# nucleo_power_supply_schematic.net
KiCad netlist of a schematic drawn in EAGLE
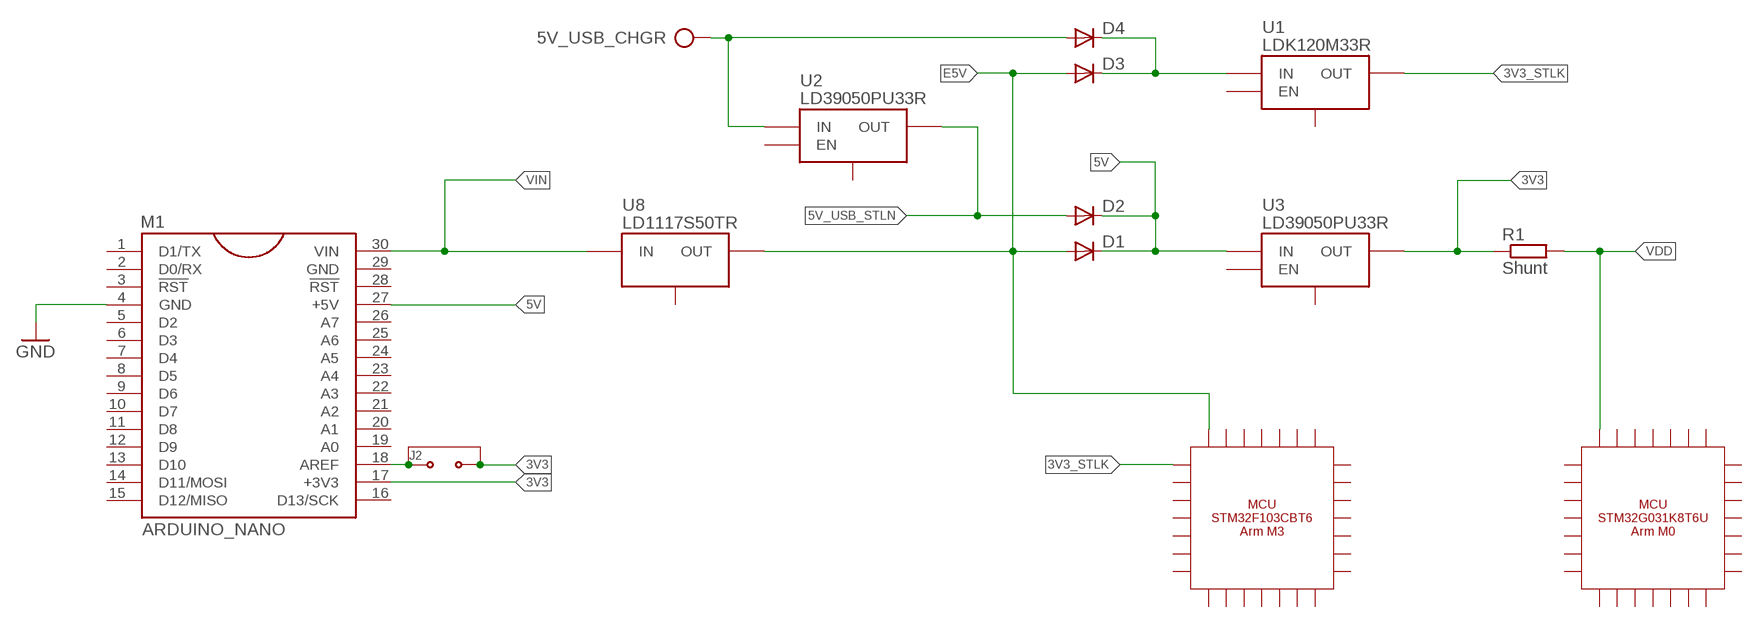
[diagram p0: schematic, sheet 1]

(export (version "E")
  (design (tool "Eeschema 10.0.6"))
  (components
    (comp (ref "D1") (value "D") (footprint "eagle-import:1X02") (libsource (lib "eagle-import") (part "D")))
    (comp (ref "D2") (value "D") (footprint "eagle-import:1X02") (libsource (lib "eagle-import") (part "D")))
    (comp (ref "D3") (value "D") (footprint "eagle-import:1X02") (libsource (lib "eagle-import") (part "D")))
    (comp (ref "D4") (value "D") (footprint "eagle-import:1X02") (libsource (lib "eagle-import") (part "D")))
    (comp (ref "J2")
      (value "CON-J2")
      (footprint "eagle-import:CON-HEADER-M-RM254-1X02")
      (libsource (lib "eagle-import") (part "CON-J2"))
    )
    (comp (ref "M1")
      (value "ARDUINO_NANO")
      (footprint "eagle-import:ARDUINO_NANO")
      (libsource (lib "eagle-import") (part "ARDUINO_NANO"))
    )
    (comp (ref "R1")
      (value "Shunt")
      (footprint "eagle-import:1X02")
      (libsource (lib "eagle-import") (part "R"))
    )
    (comp (ref "U1")
      (value "LDK120M33R")
      (footprint "eagle-import:1X04")
      (libsource (lib "eagle-import") (part "VREG04"))
    )
    (comp (ref "U2")
      (value "LD39050PU33R")
      (footprint "eagle-import:1X04")
      (libsource (lib "eagle-import") (part "VREG04"))
    )
    (comp (ref "U3")
      (value "LD39050PU33R")
      (footprint "eagle-import:1X04")
      (libsource (lib "eagle-import") (part "VREG04"))
    )
    (comp (ref "U8")
      (value "LD1117S50TR")
      (footprint "eagle-import:1X03")
      (libsource (lib "eagle-import") (part "VREG03"))
    )
    (comp (ref "X1")
      (value "5V_USB_CHGR")
      (footprint "eagle-import:1X01")
      (libsource (lib "eagle-import") (part "CON-KLEMME"))
    )
  )
  (nets
    (net (code "1") (name "3V3") (class "Default")
      (node (ref "J2") (pin "2") (pinfunction "2_2") (pintype "bidirectional"))
      (node (ref "M1") (pin "17") (pinfunction "+3V3_17") (pintype "passive"))
      (node (ref "R1") (pin "1") (pinfunction "1_1") (pintype "passive"))
      (node (ref "U3") (pin "4") (pinfunction "OUT_4") (pintype "bidirectional"))
    )
    (net (code "2") (name "3V3_STLK") (class "Default")
      (node (ref "U1") (pin "4") (pinfunction "OUT_4") (pintype "bidirectional"))
    )
    (net (code "3") (name "5V") (class "Default")
      (node (ref "D1") (pin "2") (pinfunction "C_2") (pintype "passive"))
      (node (ref "D2") (pin "2") (pinfunction "C_2") (pintype "passive"))
      (node (ref "M1") (pin "27") (pinfunction "+5V_27") (pintype "passive"))
      (node (ref "U3") (pin "3") (pinfunction "IN_3") (pintype "bidirectional"))
    )
    (net (code "4") (name "5V_USB_STLN") (class "Default")
      (node (ref "D2") (pin "1") (pinfunction "A_1") (pintype "passive"))
      (node (ref "U2") (pin "4") (pinfunction "OUT_4") (pintype "bidirectional"))
    )
    (net (code "5") (name "E5V") (class "Default")
      (node (ref "D1") (pin "1") (pinfunction "A_1") (pintype "passive"))
      (node (ref "D3") (pin "1") (pinfunction "A_1") (pintype "passive"))
      (node (ref "U8") (pin "3") (pinfunction "OUT_3") (pintype "bidirectional"))
    )
    (net (code "6") (name "GND") (class "Default")
      (node (ref "M1") (pin "4") (pinfunction "GND_4") (pintype "passive"))
    )
    (net (code "7") (name "Net-(D3-C)") (class "Default")
      (node (ref "D3") (pin "2") (pinfunction "C_2") (pintype "passive"))
      (node (ref "D4") (pin "2") (pinfunction "C_2") (pintype "passive"))
      (node (ref "U1") (pin "3") (pinfunction "IN_3") (pintype "bidirectional"))
    )
    (net (code "8") (name "Net-(D4-A)") (class "Default")
      (node (ref "D4") (pin "1") (pinfunction "A_1") (pintype "passive"))
      (node (ref "U2") (pin "3") (pinfunction "IN_3") (pintype "bidirectional"))
      (node (ref "X1") (pin "1") (pinfunction "KL_1") (pintype "passive"))
    )
    (net (code "9") (name "Net-(M1-AREF)") (class "Default")
      (node (ref "J2") (pin "1") (pinfunction "1_1") (pintype "bidirectional"))
      (node (ref "M1") (pin "18") (pinfunction "AREF_18") (pintype "passive"))
    )
    (net (code "10") (name "VDD") (class "Default")
      (node (ref "R1") (pin "2") (pinfunction "2_2") (pintype "passive"))
    )
    (net (code "11") (name "VIN") (class "Default")
      (node (ref "M1") (pin "30") (pinfunction "VIN_30") (pintype "passive"))
      (node (ref "U8") (pin "1") (pinfunction "IN_1") (pintype "bidirectional"))
    )
    (net (code "12") (name "unconnected-(M1-A0-Pad19)") (class "Default")
      (node (ref "M1") (pin "19") (pinfunction "A0_19") (pintype "bidirectional"))
    )
    (net (code "13") (name "unconnected-(M1-A1-Pad20)") (class "Default")
      (node (ref "M1") (pin "20") (pinfunction "A1_20") (pintype "bidirectional"))
    )
    (net (code "14") (name "unconnected-(M1-A2-Pad21)") (class "Default")
      (node (ref "M1") (pin "21") (pinfunction "A2_21") (pintype "bidirectional"))
    )
    (net (code "15") (name "unconnected-(M1-A3-Pad22)") (class "Default")
      (node (ref "M1") (pin "22") (pinfunction "A3_22") (pintype "bidirectional"))
    )
    (net (code "16") (name "unconnected-(M1-A4-Pad23)") (class "Default")
      (node (ref "M1") (pin "23") (pinfunction "A4_23") (pintype "bidirectional"))
    )
    (net (code "17") (name "unconnected-(M1-A5-Pad24)") (class "Default")
      (node (ref "M1") (pin "24") (pinfunction "A5_24") (pintype "bidirectional"))
    )
    (net (code "18") (name "unconnected-(M1-A6-Pad25)") (class "Default")
      (node (ref "M1") (pin "25") (pinfunction "A6_25") (pintype "bidirectional"))
    )
    (net (code "19") (name "unconnected-(M1-A7-Pad26)") (class "Default")
      (node (ref "M1") (pin "26") (pinfunction "A7_26") (pintype "bidirectional"))
    )
    (net (code "20") (name "unconnected-(M1-D0{slash}RX-Pad2)") (class "Default")
      (node (ref "M1") (pin "2") (pinfunction "D0/RX_2") (pintype "bidirectional"))
    )
    (net (code "21") (name "unconnected-(M1-D1{slash}TX-Pad1)") (class "Default")
      (node (ref "M1") (pin "1") (pinfunction "D1/TX_1") (pintype "bidirectional"))
    )
    (net (code "22") (name "unconnected-(M1-D2-Pad5)") (class "Default")
      (node (ref "M1") (pin "5") (pinfunction "D2_5") (pintype "bidirectional"))
    )
    (net (code "23") (name "unconnected-(M1-D3-Pad6)") (class "Default")
      (node (ref "M1") (pin "6") (pinfunction "D3_6") (pintype "bidirectional"))
    )
    (net (code "24") (name "unconnected-(M1-D4-Pad7)") (class "Default")
      (node (ref "M1") (pin "7") (pinfunction "D4_7") (pintype "bidirectional"))
    )
    (net (code "25") (name "unconnected-(M1-D5-Pad8)") (class "Default")
      (node (ref "M1") (pin "8") (pinfunction "D5_8") (pintype "bidirectional"))
    )
    (net (code "26") (name "unconnected-(M1-D6-Pad9)") (class "Default")
      (node (ref "M1") (pin "9") (pinfunction "D6_9") (pintype "bidirectional"))
    )
    (net (code "27") (name "unconnected-(M1-D7-Pad10)") (class "Default")
      (node (ref "M1") (pin "10") (pinfunction "D7_10") (pintype "bidirectional"))
    )
    (net (code "28") (name "unconnected-(M1-D8-Pad11)") (class "Default")
      (node (ref "M1") (pin "11") (pinfunction "D8_11") (pintype "bidirectional"))
    )
    (net (code "29") (name "unconnected-(M1-D9-Pad12)") (class "Default")
      (node (ref "M1") (pin "12") (pinfunction "D9_12") (pintype "bidirectional"))
    )
    (net (code "30") (name "unconnected-(M1-D10-Pad13)") (class "Default")
      (node (ref "M1") (pin "13") (pinfunction "D10_13") (pintype "bidirectional"))
    )
    (net (code "31") (name "unconnected-(M1-D11{slash}MOSI-Pad14)") (class "Default")
      (node (ref "M1") (pin "14") (pinfunction "D11/MOSI_14") (pintype "bidirectional"))
    )
    (net (code "32") (name "unconnected-(M1-D12{slash}MISO-Pad15)") (class "Default")
      (node (ref "M1") (pin "15") (pinfunction "D12/MISO_15") (pintype "bidirectional"))
    )
    (net (code "33") (name "unconnected-(M1-D13{slash}SCK-Pad16)") (class "Default")
      (node (ref "M1") (pin "16") (pinfunction "D13/SCK_16") (pintype "bidirectional"))
    )
    (net (code "34") (name "unconnected-(M1-GND-Pad29)") (class "Default")
      (node (ref "M1") (pin "29") (pinfunction "GND_29") (pintype "passive"))
    )
    (net (code "35") (name "unconnected-(M1-~{RST}-Pad3)") (class "Default")
      (node (ref "M1") (pin "3") (pinfunction "~{RST}_3") (pintype "input"))
    )
    (net (code "36") (name "unconnected-(M1-~{RST}-Pad28)") (class "Default")
      (node (ref "M1") (pin "28") (pinfunction "~{RST}_28") (pintype "input"))
    )
    (net (code "37") (name "unconnected-(U1-5-Pad1)") (class "Default")
      (node (ref "U1") (pin "1") (pinfunction "5_1") (pintype "bidirectional"))
    )
    (net (code "38") (name "unconnected-(U1-EN-Pad2)") (class "Default")
      (node (ref "U1") (pin "2") (pinfunction "EN_2") (pintype "bidirectional"))
    )
    (net (code "39") (name "unconnected-(U2-5-Pad1)") (class "Default")
      (node (ref "U2") (pin "1") (pinfunction "5_1") (pintype "bidirectional"))
    )
    (net (code "40") (name "unconnected-(U2-EN-Pad2)") (class "Default")
      (node (ref "U2") (pin "2") (pinfunction "EN_2") (pintype "bidirectional"))
    )
    (net (code "41") (name "unconnected-(U3-5-Pad1)") (class "Default")
      (node (ref "U3") (pin "1") (pinfunction "5_1") (pintype "bidirectional"))
    )
    (net (code "42") (name "unconnected-(U3-EN-Pad2)") (class "Default")
      (node (ref "U3") (pin "2") (pinfunction "EN_2") (pintype "bidirectional"))
    )
    (net (code "43") (name "unconnected-(U8-5-Pad2)") (class "Default")
      (node (ref "U8") (pin "2") (pinfunction "5_2") (pintype "bidirectional"))
    )
  )
)
